# 35.net
KiCad netlist of a schematic drawn in Altium Designer
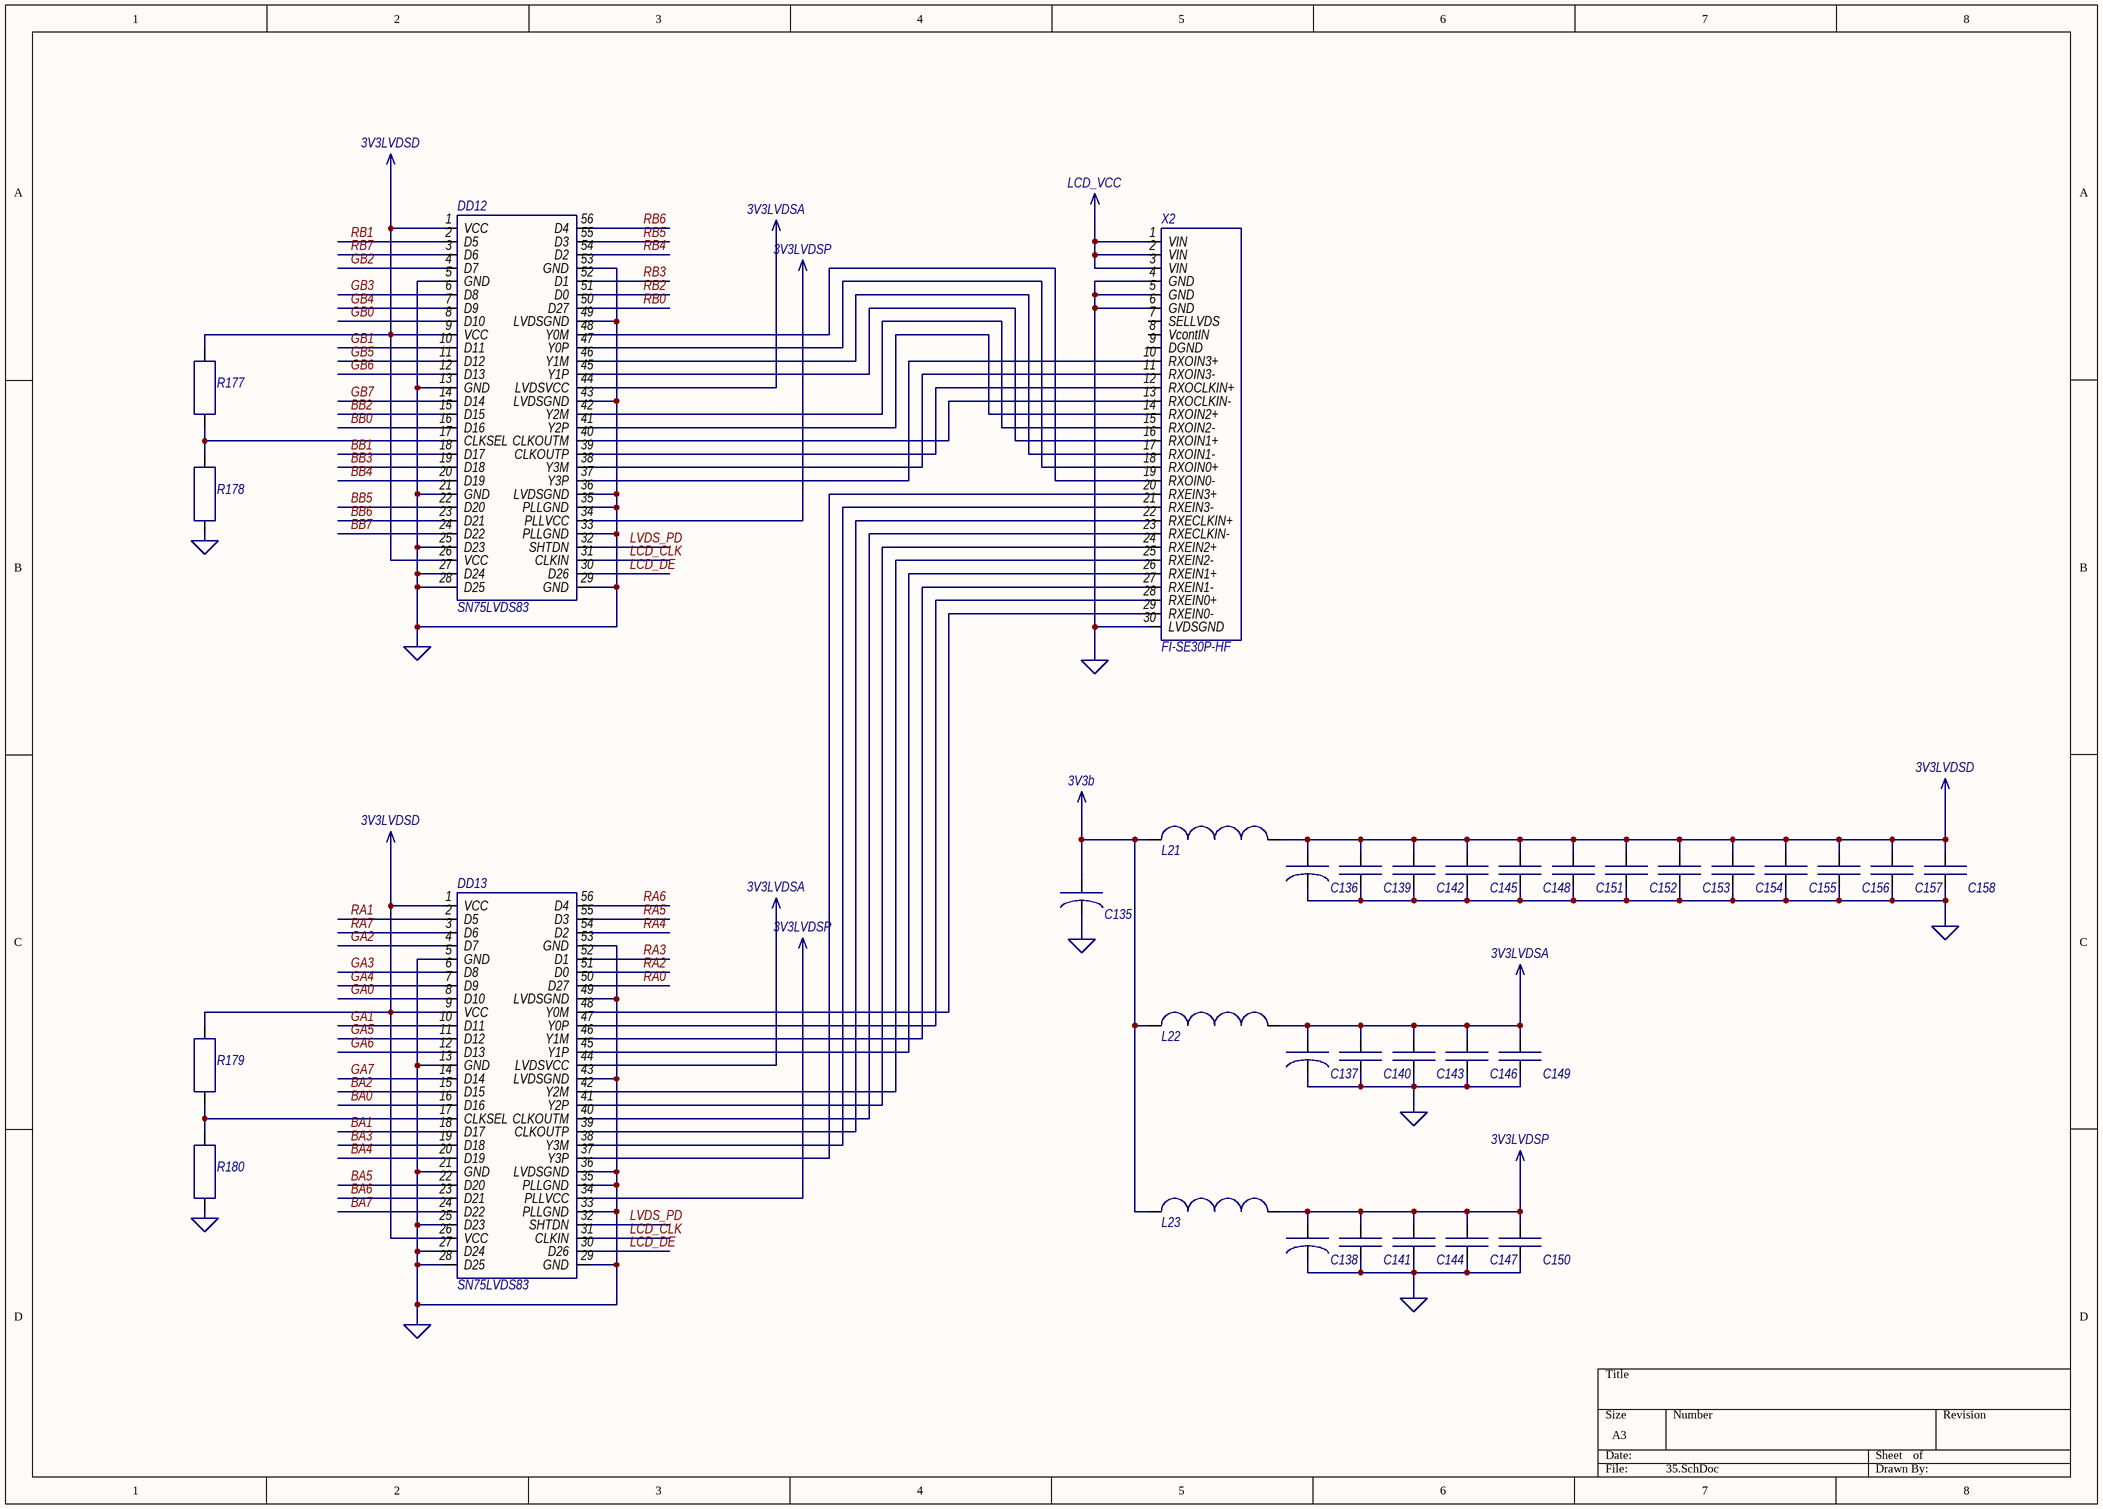
[diagram p0: 35.SchDoc]

(export (version "E")
  (design (tool "Eeschema 10.0.6"))
  (components
    (comp (ref "C135")
      (value "TuningCapacitor")
      (footprint "31_lib:Cap_tantal_D")
      (libsource (lib "31_lib") (part "TuningCapacitor"))
    )
    (comp (ref "C136")
      (value "TuningCapacitor")
      (footprint "31_lib:Cap_tantal_D")
      (libsource (lib "31_lib") (part "TuningCapacitor"))
    )
    (comp (ref "C137")
      (value "TuningCapacitor")
      (footprint "31_lib:Cap_tantal_D")
      (libsource (lib "31_lib") (part "TuningCapacitor"))
    )
    (comp (ref "C138")
      (value "TuningCapacitor")
      (footprint "31_lib:Cap_tantal_D")
      (libsource (lib "31_lib") (part "TuningCapacitor"))
    )
    (comp (ref "C139")
      (value "Capacitor")
      (footprint "cap_electro_13")
      (libsource (lib "31_lib") (part "Capacitor"))
    )
    (comp (ref "C140")
      (value "Capacitor")
      (footprint "cap_electro_13")
      (libsource (lib "31_lib") (part "Capacitor"))
    )
    (comp (ref "C141")
      (value "Capacitor")
      (footprint "cap_electro_13")
      (libsource (lib "31_lib") (part "Capacitor"))
    )
    (comp (ref "C142")
      (value "Capacitor")
      (footprint "cap_electro_13")
      (libsource (lib "31_lib") (part "Capacitor"))
    )
    (comp (ref "C143")
      (value "Capacitor")
      (footprint "cap_electro_13")
      (libsource (lib "31_lib") (part "Capacitor"))
    )
    (comp (ref "C144")
      (value "Capacitor")
      (footprint "cap_electro_13")
      (libsource (lib "31_lib") (part "Capacitor"))
    )
    (comp (ref "C145")
      (value "Capacitor")
      (footprint "cap_electro_13")
      (libsource (lib "31_lib") (part "Capacitor"))
    )
    (comp (ref "C146")
      (value "Capacitor")
      (footprint "cap_electro_13")
      (libsource (lib "31_lib") (part "Capacitor"))
    )
    (comp (ref "C147")
      (value "Capacitor")
      (footprint "cap_electro_13")
      (libsource (lib "31_lib") (part "Capacitor"))
    )
    (comp (ref "C148")
      (value "Capacitor")
      (footprint "cap_electro_13")
      (libsource (lib "31_lib") (part "Capacitor"))
    )
    (comp (ref "C149")
      (value "Capacitor")
      (footprint "cap_electro_13")
      (libsource (lib "31_lib") (part "Capacitor"))
    )
    (comp (ref "C150")
      (value "Capacitor")
      (footprint "cap_electro_13")
      (libsource (lib "31_lib") (part "Capacitor"))
    )
    (comp (ref "C151")
      (value "Capacitor")
      (footprint "cap_electro_13")
      (libsource (lib "31_lib") (part "Capacitor"))
    )
    (comp (ref "C152")
      (value "Capacitor")
      (footprint "cap_electro_13")
      (libsource (lib "31_lib") (part "Capacitor"))
    )
    (comp (ref "C153")
      (value "Capacitor")
      (footprint "cap_electro_13")
      (libsource (lib "31_lib") (part "Capacitor"))
    )
    (comp (ref "C154")
      (value "Capacitor")
      (footprint "cap_electro_13")
      (libsource (lib "31_lib") (part "Capacitor"))
    )
    (comp (ref "C155")
      (value "Capacitor")
      (footprint "cap_electro_13")
      (libsource (lib "31_lib") (part "Capacitor"))
    )
    (comp (ref "C156")
      (value "Capacitor")
      (footprint "cap_electro_13")
      (libsource (lib "31_lib") (part "Capacitor"))
    )
    (comp (ref "C157")
      (value "Capacitor")
      (footprint "cap_electro_13")
      (libsource (lib "31_lib") (part "Capacitor"))
    )
    (comp (ref "C158")
      (value "Capacitor")
      (footprint "cap_electro_13")
      (libsource (lib "31_lib") (part "Capacitor"))
    )
    (comp (ref "DD12")
      (value "SN75LVDS83")
      (footprint "31_lib:SN75LVDS83_v2")
      (libsource (lib "31_lib") (part "SN75LVDS83"))
    )
    (comp (ref "DD13")
      (value "SN75LVDS83")
      (footprint "31_lib:SN75LVDS83_v2")
      (libsource (lib "31_lib") (part "SN75LVDS83"))
    )
    (comp (ref "L21")
      (value "Inductor")
      (footprint "31_lib:inductor")
      (libsource (lib "31_lib") (part "Inductor"))
    )
    (comp (ref "L22")
      (value "Inductor")
      (footprint "31_lib:inductor")
      (libsource (lib "31_lib") (part "Inductor"))
    )
    (comp (ref "L23")
      (value "Inductor")
      (footprint "31_lib:inductor")
      (libsource (lib "31_lib") (part "Inductor"))
    )
    (comp (ref "R177")
      (value "Resistor")
      (footprint "lab_7_footprints:R_1206")
      (libsource (lib "31_lib") (part "Resistor"))
    )
    (comp (ref "R178")
      (value "Resistor")
      (footprint "lab_7_footprints:R_1206")
      (libsource (lib "31_lib") (part "Resistor"))
    )
    (comp (ref "R179")
      (value "Resistor")
      (footprint "lab_7_footprints:R_1206")
      (libsource (lib "31_lib") (part "Resistor"))
    )
    (comp (ref "R180")
      (value "Resistor")
      (footprint "lab_7_footprints:R_1206")
      (libsource (lib "31_lib") (part "Resistor"))
    )
    (comp (ref "X2")
      (value "FI-SE30P-HF")
      (footprint "31_lib:FI-SE30P-HF_v2")
      (libsource (lib "31_lib") (part "FI-SE30P-HF"))
    )
  )
  (nets
    (net (code "1") (name "/BA0") (class "Default")
      (node (ref "DD13") (pin "16") (pinfunction "D16_16") (pintype "passive"))
    )
    (net (code "2") (name "/BA1") (class "Default")
      (node (ref "DD13") (pin "18") (pinfunction "D17_18") (pintype "passive"))
    )
    (net (code "3") (name "/BA2") (class "Default")
      (node (ref "DD13") (pin "15") (pinfunction "D15_15") (pintype "passive"))
    )
    (net (code "4") (name "/BA3") (class "Default")
      (node (ref "DD13") (pin "19") (pinfunction "D18_19") (pintype "passive"))
    )
    (net (code "5") (name "/BA4") (class "Default")
      (node (ref "DD13") (pin "20") (pinfunction "D19_20") (pintype "passive"))
    )
    (net (code "6") (name "/BA5") (class "Default")
      (node (ref "DD13") (pin "22") (pinfunction "D20_22") (pintype "passive"))
    )
    (net (code "7") (name "/BA6") (class "Default")
      (node (ref "DD13") (pin "23") (pinfunction "D21_23") (pintype "passive"))
    )
    (net (code "8") (name "/BA7") (class "Default")
      (node (ref "DD13") (pin "24") (pinfunction "D22_24") (pintype "passive"))
    )
    (net (code "9") (name "/BB0") (class "Default")
      (node (ref "DD12") (pin "16") (pinfunction "D16_16") (pintype "passive"))
    )
    (net (code "10") (name "/BB1") (class "Default")
      (node (ref "DD12") (pin "18") (pinfunction "D17_18") (pintype "passive"))
    )
    (net (code "11") (name "/BB2") (class "Default")
      (node (ref "DD12") (pin "15") (pinfunction "D15_15") (pintype "passive"))
    )
    (net (code "12") (name "/BB3") (class "Default")
      (node (ref "DD12") (pin "19") (pinfunction "D18_19") (pintype "passive"))
    )
    (net (code "13") (name "/BB4") (class "Default")
      (node (ref "DD12") (pin "20") (pinfunction "D19_20") (pintype "passive"))
    )
    (net (code "14") (name "/BB5") (class "Default")
      (node (ref "DD12") (pin "22") (pinfunction "D20_22") (pintype "passive"))
    )
    (net (code "15") (name "/BB6") (class "Default")
      (node (ref "DD12") (pin "23") (pinfunction "D21_23") (pintype "passive"))
    )
    (net (code "16") (name "/BB7") (class "Default")
      (node (ref "DD12") (pin "24") (pinfunction "D22_24") (pintype "passive"))
    )
    (net (code "17") (name "/GA0") (class "Default")
      (node (ref "DD13") (pin "8") (pinfunction "D10_8") (pintype "passive"))
    )
    (net (code "18") (name "/GA1") (class "Default")
      (node (ref "DD13") (pin "10") (pinfunction "D11_10") (pintype "passive"))
    )
    (net (code "19") (name "/GA2") (class "Default")
      (node (ref "DD13") (pin "4") (pinfunction "D7_4") (pintype "passive"))
    )
    (net (code "20") (name "/GA3") (class "Default")
      (node (ref "DD13") (pin "6") (pinfunction "D8_6") (pintype "passive"))
    )
    (net (code "21") (name "/GA4") (class "Default")
      (node (ref "DD13") (pin "7") (pinfunction "D9_7") (pintype "passive"))
    )
    (net (code "22") (name "/GA5") (class "Default")
      (node (ref "DD13") (pin "11") (pinfunction "D12_11") (pintype "passive"))
    )
    (net (code "23") (name "/GA6") (class "Default")
      (node (ref "DD13") (pin "12") (pinfunction "D13_12") (pintype "passive"))
    )
    (net (code "24") (name "/GA7") (class "Default")
      (node (ref "DD13") (pin "14") (pinfunction "D14_14") (pintype "passive"))
    )
    (net (code "25") (name "/GB0") (class "Default")
      (node (ref "DD12") (pin "8") (pinfunction "D10_8") (pintype "passive"))
    )
    (net (code "26") (name "/GB1") (class "Default")
      (node (ref "DD12") (pin "10") (pinfunction "D11_10") (pintype "passive"))
    )
    (net (code "27") (name "/GB2") (class "Default")
      (node (ref "DD12") (pin "4") (pinfunction "D7_4") (pintype "passive"))
    )
    (net (code "28") (name "/GB3") (class "Default")
      (node (ref "DD12") (pin "6") (pinfunction "D8_6") (pintype "passive"))
    )
    (net (code "29") (name "/GB4") (class "Default")
      (node (ref "DD12") (pin "7") (pinfunction "D9_7") (pintype "passive"))
    )
    (net (code "30") (name "/GB5") (class "Default")
      (node (ref "DD12") (pin "11") (pinfunction "D12_11") (pintype "passive"))
    )
    (net (code "31") (name "/GB6") (class "Default")
      (node (ref "DD12") (pin "12") (pinfunction "D13_12") (pintype "passive"))
    )
    (net (code "32") (name "/GB7") (class "Default")
      (node (ref "DD12") (pin "14") (pinfunction "D14_14") (pintype "passive"))
    )
    (net (code "33") (name "/LCD_CLK") (class "Default")
      (node (ref "DD12") (pin "31") (pinfunction "CLKIN_31") (pintype "passive"))
      (node (ref "DD13") (pin "31") (pinfunction "CLKIN_31") (pintype "passive"))
    )
    (net (code "34") (name "/LCD_DE") (class "Default")
      (node (ref "DD12") (pin "30") (pinfunction "D26_30") (pintype "passive"))
      (node (ref "DD13") (pin "30") (pinfunction "D26_30") (pintype "passive"))
    )
    (net (code "35") (name "/LVDS_PD") (class "Default")
      (node (ref "DD12") (pin "32") (pinfunction "SHTDN_32") (pintype "passive"))
      (node (ref "DD13") (pin "32") (pinfunction "SHTDN_32") (pintype "passive"))
    )
    (net (code "36") (name "/RA0") (class "Default")
      (node (ref "DD13") (pin "50") (pinfunction "D27_50") (pintype "passive"))
    )
    (net (code "37") (name "/RA1") (class "Default")
      (node (ref "DD13") (pin "2") (pinfunction "D5_2") (pintype "passive"))
    )
    (net (code "38") (name "/RA2") (class "Default")
      (node (ref "DD13") (pin "51") (pinfunction "D0_51") (pintype "passive"))
    )
    (net (code "39") (name "/RA3") (class "Default")
      (node (ref "DD13") (pin "52") (pinfunction "D1_52") (pintype "passive"))
    )
    (net (code "40") (name "/RA4") (class "Default")
      (node (ref "DD13") (pin "54") (pinfunction "D2_54") (pintype "passive"))
    )
    (net (code "41") (name "/RA5") (class "Default")
      (node (ref "DD13") (pin "55") (pinfunction "D3_55") (pintype "passive"))
    )
    (net (code "42") (name "/RA6") (class "Default")
      (node (ref "DD13") (pin "56") (pinfunction "D4_56") (pintype "passive"))
    )
    (net (code "43") (name "/RA7") (class "Default")
      (node (ref "DD13") (pin "3") (pinfunction "D6_3") (pintype "passive"))
    )
    (net (code "44") (name "/RB0") (class "Default")
      (node (ref "DD12") (pin "50") (pinfunction "D27_50") (pintype "passive"))
    )
    (net (code "45") (name "/RB1") (class "Default")
      (node (ref "DD12") (pin "2") (pinfunction "D5_2") (pintype "passive"))
    )
    (net (code "46") (name "/RB2") (class "Default")
      (node (ref "DD12") (pin "51") (pinfunction "D0_51") (pintype "passive"))
    )
    (net (code "47") (name "/RB3") (class "Default")
      (node (ref "DD12") (pin "52") (pinfunction "D1_52") (pintype "passive"))
    )
    (net (code "48") (name "/RB4") (class "Default")
      (node (ref "DD12") (pin "54") (pinfunction "D2_54") (pintype "passive"))
    )
    (net (code "49") (name "/RB5") (class "Default")
      (node (ref "DD12") (pin "55") (pinfunction "D3_55") (pintype "passive"))
    )
    (net (code "50") (name "/RB6") (class "Default")
      (node (ref "DD12") (pin "56") (pinfunction "D4_56") (pintype "passive"))
    )
    (net (code "51") (name "/RB7") (class "Default")
      (node (ref "DD12") (pin "3") (pinfunction "D6_3") (pintype "passive"))
    )
    (net (code "52") (name "3V3LVDSA") (class "Default")
      (node (ref "C137") (pin "1") (pinfunction "1_1") (pintype "passive"))
      (node (ref "C140") (pin "2") (pinfunction "2_2") (pintype "passive"))
      (node (ref "C143") (pin "2") (pinfunction "2_2") (pintype "passive"))
      (node (ref "C146") (pin "2") (pinfunction "2_2") (pintype "passive"))
      (node (ref "C149") (pin "2") (pinfunction "2_2") (pintype "passive"))
      (node (ref "DD12") (pin "44") (pinfunction "LVDSVCC_44") (pintype "passive"))
      (node (ref "DD13") (pin "44") (pinfunction "LVDSVCC_44") (pintype "passive"))
      (node (ref "L22") (pin "2") (pinfunction "2_2") (pintype "passive"))
    )
    (net (code "53") (name "3V3LVDSD") (class "Default")
      (node (ref "C136") (pin "1") (pinfunction "1_1") (pintype "passive"))
      (node (ref "C139") (pin "2") (pinfunction "2_2") (pintype "passive"))
      (node (ref "C142") (pin "2") (pinfunction "2_2") (pintype "passive"))
      (node (ref "C145") (pin "2") (pinfunction "2_2") (pintype "passive"))
      (node (ref "C148") (pin "2") (pinfunction "2_2") (pintype "passive"))
      (node (ref "C151") (pin "2") (pinfunction "2_2") (pintype "passive"))
      (node (ref "C152") (pin "2") (pinfunction "2_2") (pintype "passive"))
      (node (ref "C153") (pin "2") (pinfunction "2_2") (pintype "passive"))
      (node (ref "C154") (pin "2") (pinfunction "2_2") (pintype "passive"))
      (node (ref "C155") (pin "2") (pinfunction "2_2") (pintype "passive"))
      (node (ref "C156") (pin "2") (pinfunction "2_2") (pintype "passive"))
      (node (ref "C157") (pin "2") (pinfunction "2_2") (pintype "passive"))
      (node (ref "C158") (pin "2") (pinfunction "2_2") (pintype "passive"))
      (node (ref "DD12") (pin "1") (pinfunction "VCC_1") (pintype "passive"))
      (node (ref "DD12") (pin "26") (pinfunction "VCC_26") (pintype "passive"))
      (node (ref "DD12") (pin "9") (pinfunction "VCC_9") (pintype "passive"))
      (node (ref "DD13") (pin "1") (pinfunction "VCC_1") (pintype "passive"))
      (node (ref "DD13") (pin "26") (pinfunction "VCC_26") (pintype "passive"))
      (node (ref "DD13") (pin "9") (pinfunction "VCC_9") (pintype "passive"))
      (node (ref "L21") (pin "2") (pinfunction "2_2") (pintype "passive"))
      (node (ref "R177") (pin "2") (pinfunction "2_2") (pintype "passive"))
      (node (ref "R179") (pin "2") (pinfunction "2_2") (pintype "passive"))
    )
    (net (code "54") (name "3V3LVDSP") (class "Default")
      (node (ref "C138") (pin "1") (pinfunction "1_1") (pintype "passive"))
      (node (ref "C141") (pin "2") (pinfunction "2_2") (pintype "passive"))
      (node (ref "C144") (pin "2") (pinfunction "2_2") (pintype "passive"))
      (node (ref "C147") (pin "2") (pinfunction "2_2") (pintype "passive"))
      (node (ref "C150") (pin "2") (pinfunction "2_2") (pintype "passive"))
      (node (ref "DD12") (pin "34") (pinfunction "PLLVCC_34") (pintype "passive"))
      (node (ref "DD13") (pin "34") (pinfunction "PLLVCC_34") (pintype "passive"))
      (node (ref "L23") (pin "2") (pinfunction "2_2") (pintype "passive"))
    )
    (net (code "55") (name "3V3b") (class "Default")
      (node (ref "C135") (pin "1") (pinfunction "1_1") (pintype "passive"))
      (node (ref "L21") (pin "1") (pinfunction "1_1") (pintype "passive"))
      (node (ref "L22") (pin "1") (pinfunction "1_1") (pintype "passive"))
      (node (ref "L23") (pin "1") (pinfunction "1_1") (pintype "passive"))
    )
    (net (code "56") (name "GND") (class "Default")
      (node (ref "C135") (pin "2") (pinfunction "2_2") (pintype "passive"))
      (node (ref "C136") (pin "2") (pinfunction "2_2") (pintype "passive"))
      (node (ref "C137") (pin "2") (pinfunction "2_2") (pintype "passive"))
      (node (ref "C138") (pin "2") (pinfunction "2_2") (pintype "passive"))
      (node (ref "C139") (pin "1") (pinfunction "1_1") (pintype "passive"))
      (node (ref "C140") (pin "1") (pinfunction "1_1") (pintype "passive"))
      (node (ref "C141") (pin "1") (pinfunction "1_1") (pintype "passive"))
      (node (ref "C142") (pin "1") (pinfunction "1_1") (pintype "passive"))
      (node (ref "C143") (pin "1") (pinfunction "1_1") (pintype "passive"))
      (node (ref "C144") (pin "1") (pinfunction "1_1") (pintype "passive"))
      (node (ref "C145") (pin "1") (pinfunction "1_1") (pintype "passive"))
      (node (ref "C146") (pin "1") (pinfunction "1_1") (pintype "passive"))
      (node (ref "C147") (pin "1") (pinfunction "1_1") (pintype "passive"))
      (node (ref "C148") (pin "1") (pinfunction "1_1") (pintype "passive"))
      (node (ref "C149") (pin "1") (pinfunction "1_1") (pintype "passive"))
      (node (ref "C150") (pin "1") (pinfunction "1_1") (pintype "passive"))
      (node (ref "C151") (pin "1") (pinfunction "1_1") (pintype "passive"))
      (node (ref "C152") (pin "1") (pinfunction "1_1") (pintype "passive"))
      (node (ref "C153") (pin "1") (pinfunction "1_1") (pintype "passive"))
      (node (ref "C154") (pin "1") (pinfunction "1_1") (pintype "passive"))
      (node (ref "C155") (pin "1") (pinfunction "1_1") (pintype "passive"))
      (node (ref "C156") (pin "1") (pinfunction "1_1") (pintype "passive"))
      (node (ref "C157") (pin "1") (pinfunction "1_1") (pintype "passive"))
      (node (ref "C158") (pin "1") (pinfunction "1_1") (pintype "passive"))
      (node (ref "DD12") (pin "13") (pinfunction "GND_13") (pintype "passive"))
      (node (ref "DD12") (pin "21") (pinfunction "GND_21") (pintype "passive"))
      (node (ref "DD12") (pin "25") (pinfunction "D23_25") (pintype "passive"))
      (node (ref "DD12") (pin "27") (pinfunction "D24_27") (pintype "passive"))
      (node (ref "DD12") (pin "28") (pinfunction "D25_28") (pintype "passive"))
      (node (ref "DD12") (pin "29") (pinfunction "GND_29") (pintype "passive"))
      (node (ref "DD12") (pin "33") (pinfunction "PLLGND_33") (pintype "passive"))
      (node (ref "DD12") (pin "35") (pinfunction "PLLGND_35") (pintype "passive"))
      (node (ref "DD12") (pin "36") (pinfunction "LVDSGND_36") (pintype "passive"))
      (node (ref "DD12") (pin "43") (pinfunction "LVDSGND_43") (pintype "passive"))
      (node (ref "DD12") (pin "49") (pinfunction "LVDSGND_49") (pintype "passive"))
      (node (ref "DD12") (pin "5") (pinfunction "GND_5") (pintype "passive"))
      (node (ref "DD12") (pin "53") (pinfunction "GND_53") (pintype "passive"))
      (node (ref "DD13") (pin "13") (pinfunction "GND_13") (pintype "passive"))
      (node (ref "DD13") (pin "21") (pinfunction "GND_21") (pintype "passive"))
      (node (ref "DD13") (pin "25") (pinfunction "D23_25") (pintype "passive"))
      (node (ref "DD13") (pin "27") (pinfunction "D24_27") (pintype "passive"))
      (node (ref "DD13") (pin "28") (pinfunction "D25_28") (pintype "passive"))
      (node (ref "DD13") (pin "29") (pinfunction "GND_29") (pintype "passive"))
      (node (ref "DD13") (pin "33") (pinfunction "PLLGND_33") (pintype "passive"))
      (node (ref "DD13") (pin "35") (pinfunction "PLLGND_35") (pintype "passive"))
      (node (ref "DD13") (pin "36") (pinfunction "LVDSGND_36") (pintype "passive"))
      (node (ref "DD13") (pin "43") (pinfunction "LVDSGND_43") (pintype "passive"))
      (node (ref "DD13") (pin "49") (pinfunction "LVDSGND_49") (pintype "passive"))
      (node (ref "DD13") (pin "5") (pinfunction "GND_5") (pintype "passive"))
      (node (ref "DD13") (pin "53") (pinfunction "GND_53") (pintype "passive"))
      (node (ref "R178") (pin "1") (pinfunction "1_1") (pintype "passive"))
      (node (ref "R180") (pin "1") (pinfunction "1_1") (pintype "passive"))
      (node (ref "X2") (pin "30") (pinfunction "LVDSGND_30") (pintype "passive"))
      (node (ref "X2") (pin "4") (pinfunction "GND_4") (pintype "passive"))
      (node (ref "X2") (pin "5") (pinfunction "GND_5") (pintype "passive"))
      (node (ref "X2") (pin "6") (pinfunction "GND_6") (pintype "passive"))
    )
    (net (code "57") (name "LCD_VCC") (class "Default")
      (node (ref "X2") (pin "1") (pinfunction "VIN_1") (pintype "passive"))
      (node (ref "X2") (pin "2") (pinfunction "VIN_2") (pintype "passive"))
      (node (ref "X2") (pin "3") (pinfunction "VIN_3") (pintype "passive"))
    )
    (net (code "58") (name "Net-(DD12-CLKOUTM)") (class "Default")
      (node (ref "DD12") (pin "40") (pinfunction "CLKOUTM_40") (pintype "passive"))
      (node (ref "X2") (pin "13") (pinfunction "RXOCLKIN-_13") (pintype "passive"))
    )
    (net (code "59") (name "Net-(DD12-CLKOUTP)") (class "Default")
      (node (ref "DD12") (pin "39") (pinfunction "CLKOUTP_39") (pintype "passive"))
      (node (ref "X2") (pin "12") (pinfunction "RXOCLKIN+_12") (pintype "passive"))
    )
    (net (code "60") (name "Net-(DD12-CLKSEL)") (class "Default")
      (node (ref "DD12") (pin "17") (pinfunction "CLKSEL_17") (pintype "passive"))
      (node (ref "R177") (pin "1") (pinfunction "1_1") (pintype "passive"))
      (node (ref "R178") (pin "2") (pinfunction "2_2") (pintype "passive"))
    )
    (net (code "61") (name "Net-(DD12-Y0M)") (class "Default")
      (node (ref "DD12") (pin "48") (pinfunction "Y0M_48") (pintype "passive"))
      (node (ref "X2") (pin "19") (pinfunction "RXOIN0-_19") (pintype "passive"))
    )
    (net (code "62") (name "Net-(DD12-Y0P)") (class "Default")
      (node (ref "DD12") (pin "47") (pinfunction "Y0P_47") (pintype "passive"))
      (node (ref "X2") (pin "18") (pinfunction "RXOIN0+_18") (pintype "passive"))
    )
    (net (code "63") (name "Net-(DD12-Y1M)") (class "Default")
      (node (ref "DD12") (pin "46") (pinfunction "Y1M_46") (pintype "passive"))
      (node (ref "X2") (pin "17") (pinfunction "RXOIN1-_17") (pintype "passive"))
    )
    (net (code "64") (name "Net-(DD12-Y1P)") (class "Default")
      (node (ref "DD12") (pin "45") (pinfunction "Y1P_45") (pintype "passive"))
      (node (ref "X2") (pin "16") (pinfunction "RXOIN1+_16") (pintype "passive"))
    )
    (net (code "65") (name "Net-(DD12-Y2M)") (class "Default")
      (node (ref "DD12") (pin "42") (pinfunction "Y2M_42") (pintype "passive"))
      (node (ref "X2") (pin "15") (pinfunction "RXOIN2-_15") (pintype "passive"))
    )
    (net (code "66") (name "Net-(DD12-Y2P)") (class "Default")
      (node (ref "DD12") (pin "41") (pinfunction "Y2P_41") (pintype "passive"))
      (node (ref "X2") (pin "14") (pinfunction "RXOIN2+_14") (pintype "passive"))
    )
    (net (code "67") (name "Net-(DD12-Y3M)") (class "Default")
      (node (ref "DD12") (pin "38") (pinfunction "Y3M_38") (pintype "passive"))
      (node (ref "X2") (pin "11") (pinfunction "RXOIN3-_11") (pintype "passive"))
    )
    (net (code "68") (name "Net-(DD12-Y3P)") (class "Default")
      (node (ref "DD12") (pin "37") (pinfunction "Y3P_37") (pintype "passive"))
      (node (ref "X2") (pin "10") (pinfunction "RXOIN3+_10") (pintype "passive"))
    )
    (net (code "69") (name "Net-(DD13-CLKOUTM)") (class "Default")
      (node (ref "DD13") (pin "40") (pinfunction "CLKOUTM_40") (pintype "passive"))
      (node (ref "X2") (pin "23") (pinfunction "RXECLKIN-_23") (pintype "passive"))
    )
    (net (code "70") (name "Net-(DD13-CLKOUTP)") (class "Default")
      (node (ref "DD13") (pin "39") (pinfunction "CLKOUTP_39") (pintype "passive"))
      (node (ref "X2") (pin "22") (pinfunction "RXECLKIN+_22") (pintype "passive"))
    )
    (net (code "71") (name "Net-(DD13-CLKSEL)") (class "Default")
      (node (ref "DD13") (pin "17") (pinfunction "CLKSEL_17") (pintype "passive"))
      (node (ref "R179") (pin "1") (pinfunction "1_1") (pintype "passive"))
      (node (ref "R180") (pin "2") (pinfunction "2_2") (pintype "passive"))
    )
    (net (code "72") (name "Net-(DD13-Y0M)") (class "Default")
      (node (ref "DD13") (pin "48") (pinfunction "Y0M_48") (pintype "passive"))
      (node (ref "X2") (pin "29") (pinfunction "RXEIN0-_29") (pintype "passive"))
    )
    (net (code "73") (name "Net-(DD13-Y0P)") (class "Default")
      (node (ref "DD13") (pin "47") (pinfunction "Y0P_47") (pintype "passive"))
      (node (ref "X2") (pin "28") (pinfunction "RXEIN0+_28") (pintype "passive"))
    )
    (net (code "74") (name "Net-(DD13-Y1M)") (class "Default")
      (node (ref "DD13") (pin "46") (pinfunction "Y1M_46") (pintype "passive"))
      (node (ref "X2") (pin "27") (pinfunction "RXEIN1-_27") (pintype "passive"))
    )
    (net (code "75") (name "Net-(DD13-Y1P)") (class "Default")
      (node (ref "DD13") (pin "45") (pinfunction "Y1P_45") (pintype "passive"))
      (node (ref "X2") (pin "26") (pinfunction "RXEIN1+_26") (pintype "passive"))
    )
    (net (code "76") (name "Net-(DD13-Y2M)") (class "Default")
      (node (ref "DD13") (pin "42") (pinfunction "Y2M_42") (pintype "passive"))
      (node (ref "X2") (pin "25") (pinfunction "RXEIN2-_25") (pintype "passive"))
    )
    (net (code "77") (name "Net-(DD13-Y2P)") (class "Default")
      (node (ref "DD13") (pin "41") (pinfunction "Y2P_41") (pintype "passive"))
      (node (ref "X2") (pin "24") (pinfunction "RXEIN2+_24") (pintype "passive"))
    )
    (net (code "78") (name "Net-(DD13-Y3M)") (class "Default")
      (node (ref "DD13") (pin "38") (pinfunction "Y3M_38") (pintype "passive"))
      (node (ref "X2") (pin "21") (pinfunction "RXEIN3-_21") (pintype "passive"))
    )
    (net (code "79") (name "Net-(DD13-Y3P)") (class "Default")
      (node (ref "DD13") (pin "37") (pinfunction "Y3P_37") (pintype "passive"))
      (node (ref "X2") (pin "20") (pinfunction "RXEIN3+_20") (pintype "passive"))
    )
    (net (code "80") (name "unconnected-(X2-DGND-Pad9)") (class "Default")
      (node (ref "X2") (pin "9") (pinfunction "DGND_9") (pintype "passive"))
    )
    (net (code "81") (name "unconnected-(X2-SELLVDS-Pad7)") (class "Default")
      (node (ref "X2") (pin "7") (pinfunction "SELLVDS_7") (pintype "passive"))
    )
    (net (code "82") (name "unconnected-(X2-VcontIN-Pad8)") (class "Default")
      (node (ref "X2") (pin "8") (pinfunction "VcontIN_8") (pintype "passive"))
    )
  )
)
